# Power_Supply.net
KiCad netlist of a schematic drawn in Altium Designer
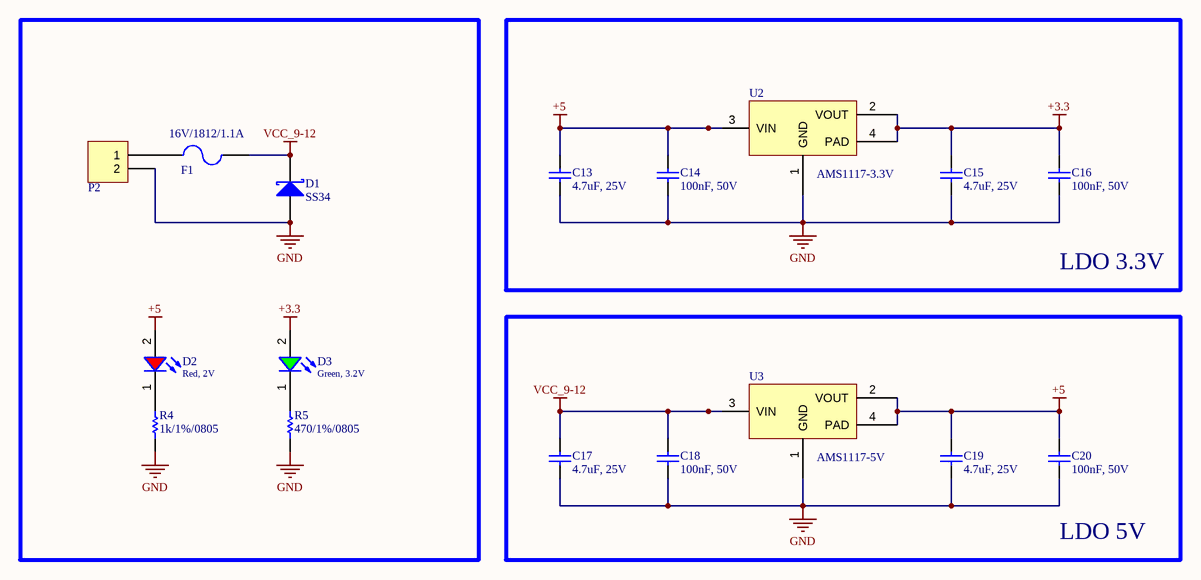
[diagram p0: Power_Supply.SchDoc]

(export (version "E")
  (design (tool "Eeschema 10.0.6"))
  (components
    (comp (ref "C13")
      (value "4.7uF, 25V")
      (footprint "WCAP-CSGP_0805_H=1.25mm")
      (description "WCAP-CSGP Multilayer Ceramic Chip Capacitor, General Purpose, size 0805, X5R, 4.7uF, 25V")
      (fields
        (field (name "MANUFACTURER PART NUMBER") "885012107018")
        (field (name "MANUFACTURER") "Wurth Elektronik")
      )
      (libsource (lib "Altium_WCAP-CSGP (rev20a)") (part "885012107018"))
    )
    (comp (ref "C14")
      (value "100nF, 50V")
      (footprint "WCAP-CSGP_0805_H=0.8mm_Wave")
      (description "WCAP-CSGP Multilayer Ceramic Chip Capacitor, General Purpose, size 0805, X7R, 100nF, 50V")
      (fields
        (field (name "MANUFACTURER PART NUMBER") "885012207098")
        (field (name "MANUFACTURER") "Wurth Elektronik")
      )
      (libsource (lib "Altium_WCAP-CSGP (rev20a)") (part "885012207098"))
    )
    (comp (ref "C15")
      (value "4.7uF, 25V")
      (footprint "WCAP-CSGP_0805_H=1.25mm")
      (description "WCAP-CSGP Multilayer Ceramic Chip Capacitor, General Purpose, size 0805, X5R, 4.7uF, 25V")
      (fields
        (field (name "MANUFACTURER PART NUMBER") "885012107018")
        (field (name "MANUFACTURER") "Wurth Elektronik")
      )
      (libsource (lib "Altium_WCAP-CSGP (rev20a)") (part "885012107018"))
    )
    (comp (ref "C16")
      (value "100nF, 50V")
      (footprint "WCAP-CSGP_0805_H=0.8mm_Wave")
      (description "WCAP-CSGP Multilayer Ceramic Chip Capacitor, General Purpose, size 0805, X7R, 100nF, 50V")
      (fields
        (field (name "MANUFACTURER PART NUMBER") "885012207098")
        (field (name "MANUFACTURER") "Wurth Elektronik")
      )
      (libsource (lib "Altium_WCAP-CSGP (rev20a)") (part "885012207098"))
    )
    (comp (ref "C17")
      (value "4.7uF, 25V")
      (footprint "WCAP-CSGP_0805_H=1.25mm")
      (description "WCAP-CSGP Multilayer Ceramic Chip Capacitor, General Purpose, size 0805, X5R, 4.7uF, 25V")
      (fields
        (field (name "MANUFACTURER PART NUMBER") "885012107018")
        (field (name "MANUFACTURER") "Wurth Elektronik")
      )
      (libsource (lib "Altium_WCAP-CSGP (rev20a)") (part "885012107018"))
    )
    (comp (ref "C18")
      (value "100nF, 50V")
      (footprint "WCAP-CSGP_0805_H=0.8mm_Wave")
      (description "WCAP-CSGP Multilayer Ceramic Chip Capacitor, General Purpose, size 0805, X7R, 100nF, 50V")
      (fields
        (field (name "MANUFACTURER PART NUMBER") "885012207098")
        (field (name "MANUFACTURER") "Wurth Elektronik")
      )
      (libsource (lib "Altium_WCAP-CSGP (rev20a)") (part "885012207098"))
    )
    (comp (ref "C19")
      (value "4.7uF, 25V")
      (footprint "WCAP-CSGP_0805_H=1.25mm")
      (description "WCAP-CSGP Multilayer Ceramic Chip Capacitor, General Purpose, size 0805, X5R, 4.7uF, 25V")
      (fields
        (field (name "MANUFACTURER PART NUMBER") "885012107018")
        (field (name "MANUFACTURER") "Wurth Elektronik")
      )
      (libsource (lib "Altium_WCAP-CSGP (rev20a)") (part "885012107018"))
    )
    (comp (ref "C20")
      (value "100nF, 50V")
      (footprint "WCAP-CSGP_0805_H=0.8mm_Wave")
      (description "WCAP-CSGP Multilayer Ceramic Chip Capacitor, General Purpose, size 0805, X7R, 100nF, 50V")
      (fields
        (field (name "MANUFACTURER PART NUMBER") "885012207098")
        (field (name "MANUFACTURER") "Wurth Elektronik")
      )
      (libsource (lib "Altium_WCAP-CSGP (rev20a)") (part "885012207098"))
    )
    (comp (ref "D1")
      (value "D Schottky")
      (footprint "SS34")
      (description "Schottky Diode")
      (fields (field (name "SUPPLIER PART NUMBER 1") "SS34") (field (name "PUBLISHER") "Altium Limited"))
      (libsource (lib "PIF_Library") (part "D Schottky"))
    )
    (comp (ref "D2")
      (value "Red, 2V")
      (footprint "WL-SMCW_0805")
      (description "WL-SMCW SMT Mono-color Chip LED Waterclear, size 0805, Red, 2V, 140deg")
      (fields (field (name "PART NUMBER") "150080RS75000") (field (name "PUBLISHER") "Wurth Elektronik"))
      (libsource (lib "Altium_WL-SMCW (rev20a)") (part "150080RS75000"))
    )
    (comp (ref "D3")
      (value "Green, 3.2V")
      (footprint "WL-SMCW_0805")
      (description "WL-SMCW SMT Mono-color Chip LED Waterclear, size 0805, Green, 3.2V, 140deg")
      (fields (field (name "PART NUMBER") "150080GS75000") (field (name "PUBLISHER") "Wurth Elektronik"))
      (libsource (lib "Altium_WL-SMCW (rev20a)") (part "150080GS75000"))
    )
    (comp (ref "F1") (value "Fuse") (footprint "FUSE SMD") (libsource (lib "PIF_Library") (part "Fuse")))
    (comp (ref "P2")
      (value "Domino 2")
      (footprint "DOMINO 2- 5mm")
      (description "Domino, 2-Pin")
      (fields (field (name "PUBLISHER") "Altium Limited"))
      (libsource (lib "PIF_Library") (part "Domino 2"))
    )
    (comp (ref "R4")
      (value "1k/1%/0805")
      (footprint "RES-SM-0805")
      (description "Resistor")
      (fields (field (name "Comment") "RESISTOR SMD"))
      (libsource (lib "PIF_Library") (part "RESISTOR SMD"))
    )
    (comp (ref "R5")
      (value "470/1%/0805")
      (footprint "RES-SM-0805")
      (description "Resistor")
      (fields (field (name "Comment") "RESISTOR SMD"))
      (libsource (lib "PIF_Library") (part "RESISTOR SMD"))
    )
    (comp (ref "U2")
      (value "AMS1117-3.3V")
      (footprint "SOT230P700X180-4N")
      (libsource (lib "MiclsLib") (part "AMS1117-3.3V"))
    )
    (comp (ref "U3")
      (value "AMS1117-5V")
      (footprint "SOT230P700X180-4N")
      (libsource (lib "MiclsLib") (part "AMS1117-5V"))
    )
  )
  (nets
    (net (code "1") (name "+3.3") (class "Default")
      (node (ref "C15") (pin "2") (pinfunction "2_2") (pintype "passive"))
      (node (ref "C16") (pin "2") (pinfunction "2_2") (pintype "passive"))
      (node (ref "D3") (pin "2") (pinfunction "A_2") (pintype "passive"))
      (node (ref "U2") (pin "2") (pinfunction "VOUT_2") (pintype "passive"))
      (node (ref "U2") (pin "4") (pinfunction "PAD_4") (pintype "passive"))
    )
    (net (code "2") (name "+5") (class "Default")
      (node (ref "C13") (pin "2") (pinfunction "2_2") (pintype "passive"))
      (node (ref "C14") (pin "2") (pinfunction "2_2") (pintype "passive"))
      (node (ref "C19") (pin "2") (pinfunction "2_2") (pintype "passive"))
      (node (ref "C20") (pin "2") (pinfunction "2_2") (pintype "passive"))
      (node (ref "D2") (pin "2") (pinfunction "A_2") (pintype "passive"))
      (node (ref "U2") (pin "3") (pinfunction "VIN_3") (pintype "passive"))
      (node (ref "U3") (pin "2") (pinfunction "VOUT_2") (pintype "passive"))
      (node (ref "U3") (pin "4") (pinfunction "PAD_4") (pintype "passive"))
    )
    (net (code "3") (name "GND") (class "Default")
      (node (ref "C13") (pin "1") (pinfunction "1_1") (pintype "passive"))
      (node (ref "C14") (pin "1") (pinfunction "1_1") (pintype "passive"))
      (node (ref "C15") (pin "1") (pinfunction "1_1") (pintype "passive"))
      (node (ref "C16") (pin "1") (pinfunction "1_1") (pintype "passive"))
      (node (ref "C17") (pin "1") (pinfunction "1_1") (pintype "passive"))
      (node (ref "C18") (pin "1") (pinfunction "1_1") (pintype "passive"))
      (node (ref "C19") (pin "1") (pinfunction "1_1") (pintype "passive"))
      (node (ref "C20") (pin "1") (pinfunction "1_1") (pintype "passive"))
      (node (ref "D1") (pin "A") (pinfunction "A_A") (pintype "passive"))
      (node (ref "P2") (pin "2") (pinfunction "2_2") (pintype "passive"))
      (node (ref "R4") (pin "1") (pinfunction "1_1") (pintype "passive"))
      (node (ref "R5") (pin "1") (pinfunction "1_1") (pintype "passive"))
      (node (ref "U2") (pin "1") (pinfunction "GND_1") (pintype "passive"))
      (node (ref "U3") (pin "1") (pinfunction "GND_1") (pintype "passive"))
    )
    (net (code "4") (name "Net-(D2-K)") (class "Default")
      (node (ref "D2") (pin "1") (pinfunction "K_1") (pintype "passive"))
      (node (ref "R4") (pin "2") (pinfunction "2_2") (pintype "passive"))
    )
    (net (code "5") (name "Net-(D3-K)") (class "Default")
      (node (ref "D3") (pin "1") (pinfunction "K_1") (pintype "passive"))
      (node (ref "R5") (pin "2") (pinfunction "2_2") (pintype "passive"))
    )
    (net (code "6") (name "Net-(F1-Pad1)") (class "Default")
      (node (ref "F1") (pin "1") (pinfunction "1_1") (pintype "passive"))
      (node (ref "P2") (pin "1") (pinfunction "1_1") (pintype "passive"))
    )
    (net (code "7") (name "VCC_9-12") (class "Default")
      (node (ref "C17") (pin "2") (pinfunction "2_2") (pintype "passive"))
      (node (ref "C18") (pin "2") (pinfunction "2_2") (pintype "passive"))
      (node (ref "D1") (pin "K") (pinfunction "K_K") (pintype "passive"))
      (node (ref "F1") (pin "2") (pinfunction "2_2") (pintype "passive"))
      (node (ref "U3") (pin "3") (pinfunction "VIN_3") (pintype "passive"))
    )
  )
)
